# Adafruit_Si7021_Original.net
KiCad netlist of a schematic drawn in EAGLE
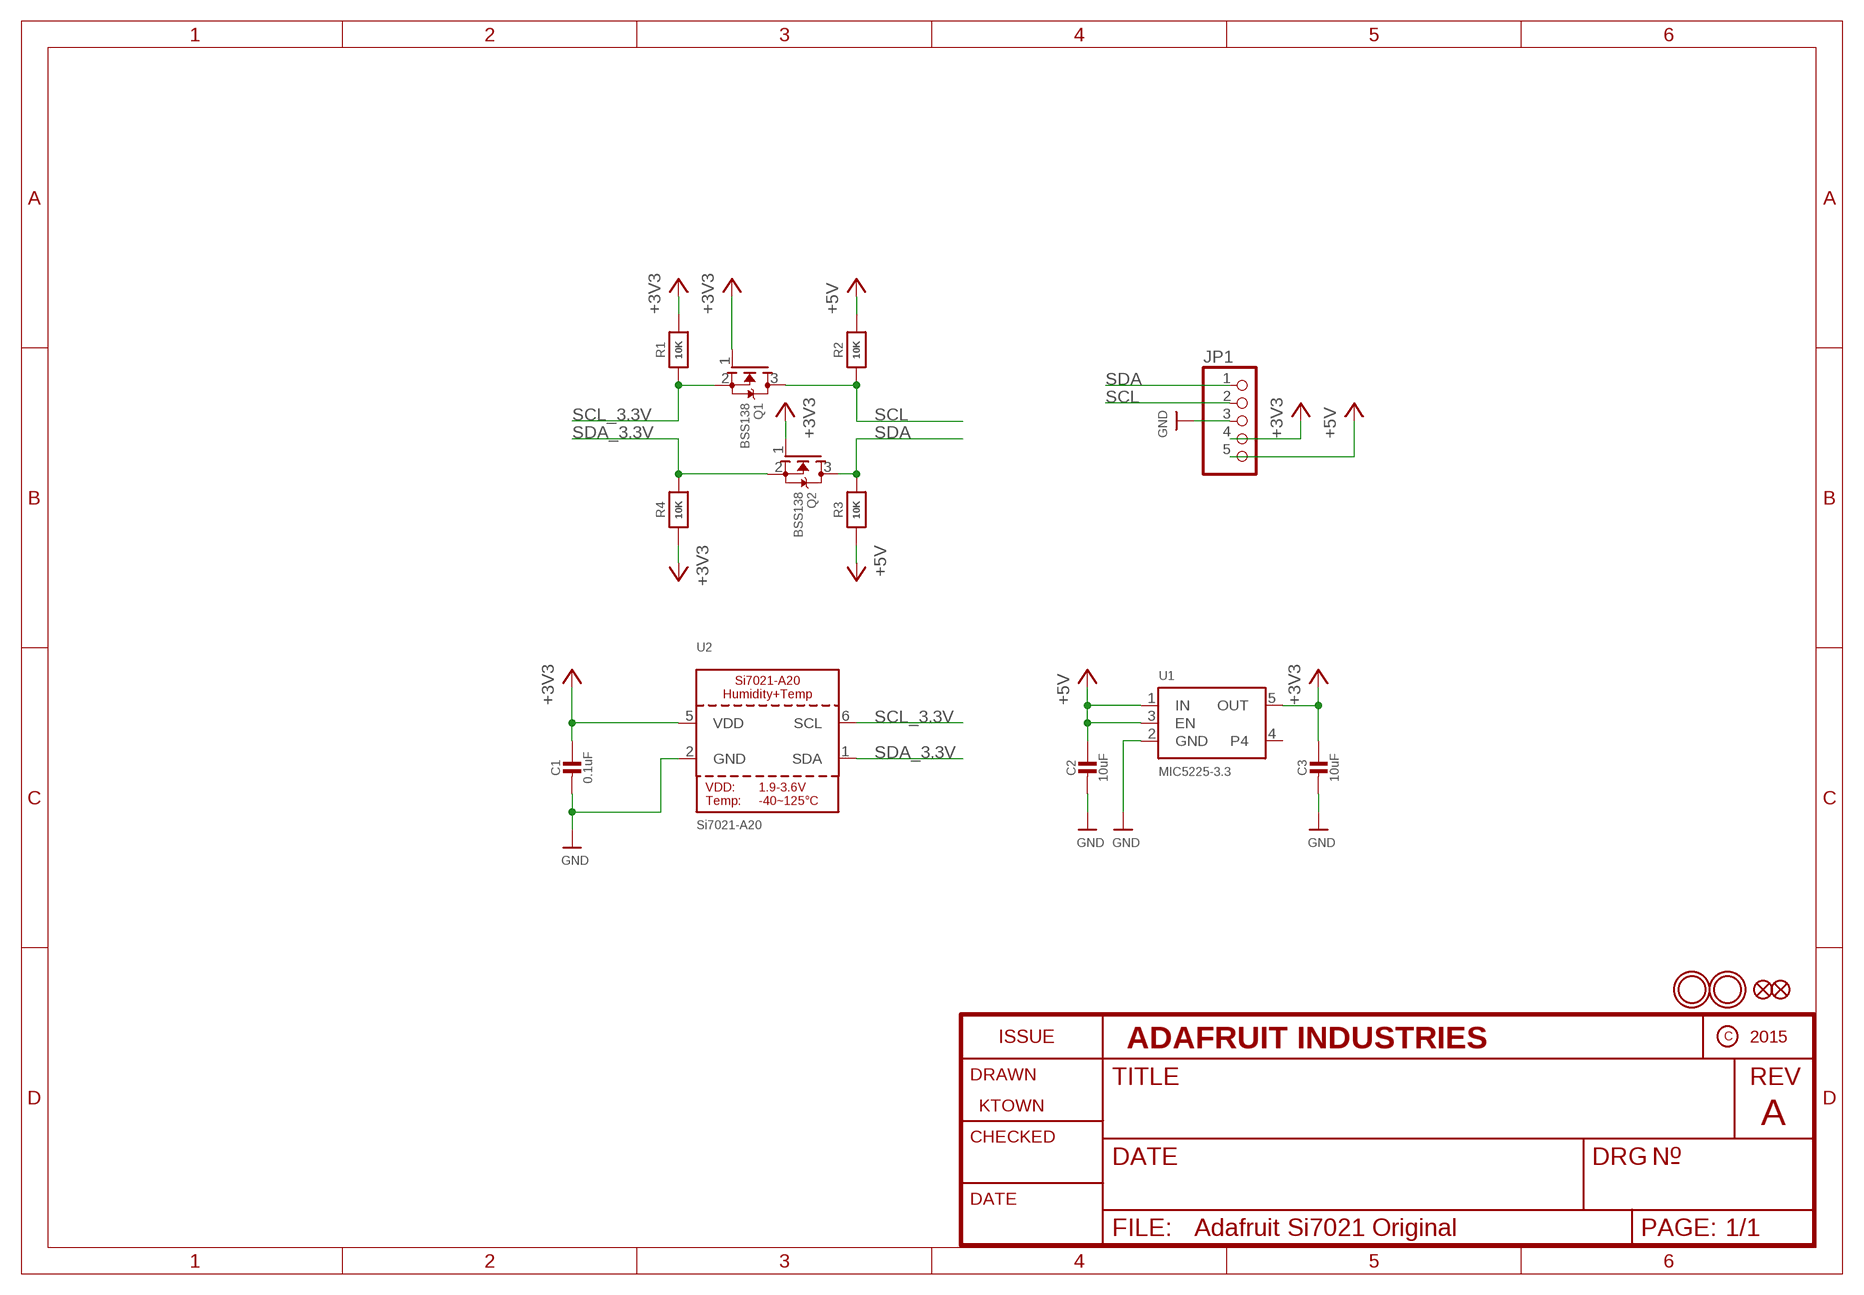
[diagram p0: schematic, sheet 1]

(export (version "E")
  (design (tool "Eeschema 10.0.6"))
  (components
    (comp (ref "C1")
      (value "0.1uF")
      (footprint "eagle-import:0805-NO")
      (libsource (lib "eagle-import") (part "CAP_CERAMIC0805-NOOUTLINE"))
    )
    (comp (ref "C2")
      (value "10uF")
      (footprint "eagle-import:0805-NO")
      (libsource (lib "eagle-import") (part "CAP_CERAMIC0805-NOOUTLINE"))
    )
    (comp (ref "C3")
      (value "10uF")
      (footprint "eagle-import:0805-NO")
      (libsource (lib "eagle-import") (part "CAP_CERAMIC0805-NOOUTLINE"))
    )
    (comp (ref "FID1")
      (value "FIDUCIAL\"\"")
      (footprint "eagle-import:FIDUCIAL_1MM")
      (libsource (lib "eagle-import") (part "FIDUCIAL{dblquote}{dblquote}"))
    )
    (comp (ref "FID2")
      (value "FIDUCIAL\"\"")
      (footprint "eagle-import:FIDUCIAL_1MM")
      (libsource (lib "eagle-import") (part "FIDUCIAL{dblquote}{dblquote}"))
    )
    (comp (ref "JP1")
      (value "HEADER-1X570MIL")
      (footprint "eagle-import:1X05_ROUND_70")
      (libsource (lib "eagle-import") (part "HEADER-1X570MIL"))
    )
    (comp (ref "Q1")
      (value "BSS138")
      (footprint "eagle-import:SOT23-WIDE")
      (libsource (lib "eagle-import") (part "MOSFET-NWIDE"))
    )
    (comp (ref "Q2")
      (value "BSS138")
      (footprint "eagle-import:SOT23-WIDE")
      (libsource (lib "eagle-import") (part "MOSFET-NWIDE"))
    )
    (comp (ref "R1")
      (value "10K")
      (footprint "eagle-import:0805-NO")
      (libsource (lib "eagle-import") (part "RESISTOR0805_NOOUTLINE"))
    )
    (comp (ref "R2")
      (value "10K")
      (footprint "eagle-import:0805-NO")
      (libsource (lib "eagle-import") (part "RESISTOR0805_NOOUTLINE"))
    )
    (comp (ref "R3")
      (value "10K")
      (footprint "eagle-import:0805-NO")
      (libsource (lib "eagle-import") (part "RESISTOR0805_NOOUTLINE"))
    )
    (comp (ref "R4")
      (value "10K")
      (footprint "eagle-import:0805-NO")
      (libsource (lib "eagle-import") (part "RESISTOR0805_NOOUTLINE"))
    )
    (comp (ref "U$6")
      (value "MOUNTINGHOLE2.5")
      (footprint "eagle-import:MOUNTINGHOLE_2.5_PLATED")
      (libsource (lib "eagle-import") (part "MOUNTINGHOLE2.5"))
    )
    (comp (ref "U$7")
      (value "MOUNTINGHOLE2.5")
      (footprint "eagle-import:MOUNTINGHOLE_2.5_PLATED")
      (libsource (lib "eagle-import") (part "MOUNTINGHOLE2.5"))
    )
    (comp (ref "U1")
      (value "MIC5225-3.3")
      (footprint "eagle-import:SOT23-5")
      (libsource (lib "eagle-import") (part "VREG_SOT23-5"))
    )
    (comp (ref "U2")
      (value "Si7021-A20")
      (footprint "eagle-import:DFN6_3X3_SI")
      (libsource (lib "eagle-import") (part "SI7021-A20"))
    )
  )
  (nets
    (net (code "1") (name "+3V3") (class "Default")
      (node (ref "C1") (pin "1") (pinfunction "1_1") (pintype "passive"))
      (node (ref "C3") (pin "1") (pinfunction "1_1") (pintype "passive"))
      (node (ref "JP1") (pin "4") (pinfunction "4_4") (pintype "passive"))
      (node (ref "Q1") (pin "1") (pinfunction "G_1") (pintype "bidirectional"))
      (node (ref "Q2") (pin "1") (pinfunction "G_1") (pintype "bidirectional"))
      (node (ref "R1") (pin "2") (pinfunction "2_2") (pintype "passive"))
      (node (ref "R4") (pin "1") (pinfunction "1_1") (pintype "passive"))
      (node (ref "U1") (pin "5") (pinfunction "OUT_5") (pintype "power_in"))
      (node (ref "U2") (pin "5") (pinfunction "VDD_5") (pintype "power_in"))
    )
    (net (code "2") (name "+5V") (class "Default")
      (node (ref "C2") (pin "1") (pinfunction "1_1") (pintype "passive"))
      (node (ref "JP1") (pin "5") (pinfunction "5_5") (pintype "passive"))
      (node (ref "R2") (pin "2") (pinfunction "2_2") (pintype "passive"))
      (node (ref "R3") (pin "1") (pinfunction "1_1") (pintype "passive"))
      (node (ref "U1") (pin "1") (pinfunction "IN_1") (pintype "power_in"))
      (node (ref "U1") (pin "3") (pinfunction "EN_3") (pintype "input"))
    )
    (net (code "3") (name "/SCL") (class "Default")
      (node (ref "JP1") (pin "2") (pinfunction "2_2") (pintype "passive"))
      (node (ref "Q1") (pin "3") (pinfunction "D_3") (pintype "bidirectional"))
      (node (ref "R2") (pin "1") (pinfunction "1_1") (pintype "passive"))
    )
    (net (code "4") (name "/SCL_3.3V") (class "Default")
      (node (ref "Q1") (pin "2") (pinfunction "S_2") (pintype "bidirectional"))
      (node (ref "R1") (pin "1") (pinfunction "1_1") (pintype "passive"))
      (node (ref "U2") (pin "6") (pinfunction "SCL_6") (pintype "open_collector"))
    )
    (net (code "5") (name "/SDA") (class "Default")
      (node (ref "JP1") (pin "1") (pinfunction "1_1") (pintype "passive"))
      (node (ref "Q2") (pin "3") (pinfunction "D_3") (pintype "bidirectional"))
      (node (ref "R3") (pin "2") (pinfunction "2_2") (pintype "passive"))
    )
    (net (code "6") (name "/SDA_3.3V") (class "Default")
      (node (ref "Q2") (pin "2") (pinfunction "S_2") (pintype "bidirectional"))
      (node (ref "R4") (pin "2") (pinfunction "2_2") (pintype "passive"))
      (node (ref "U2") (pin "1") (pinfunction "SDA_1") (pintype "open_collector"))
    )
    (net (code "7") (name "GND") (class "Default")
      (node (ref "C1") (pin "2") (pinfunction "2_2") (pintype "passive"))
      (node (ref "C2") (pin "2") (pinfunction "2_2") (pintype "passive"))
      (node (ref "C3") (pin "2") (pinfunction "2_2") (pintype "passive"))
      (node (ref "JP1") (pin "3") (pinfunction "3_3") (pintype "passive"))
      (node (ref "U1") (pin "2") (pinfunction "GND_2") (pintype "power_in"))
      (node (ref "U2") (pin "2") (pinfunction "GND_2") (pintype "power_in"))
    )
    (net (code "8") (name "unconnected-(U1-P4-Pad4)") (class "Default")
      (node (ref "U1") (pin "4") (pinfunction "P4_4") (pintype "bidirectional"))
    )
  )
)
